# SOIC8-TSSOP8_v1_0.net
KiCad netlist of a schematic drawn in EAGLE
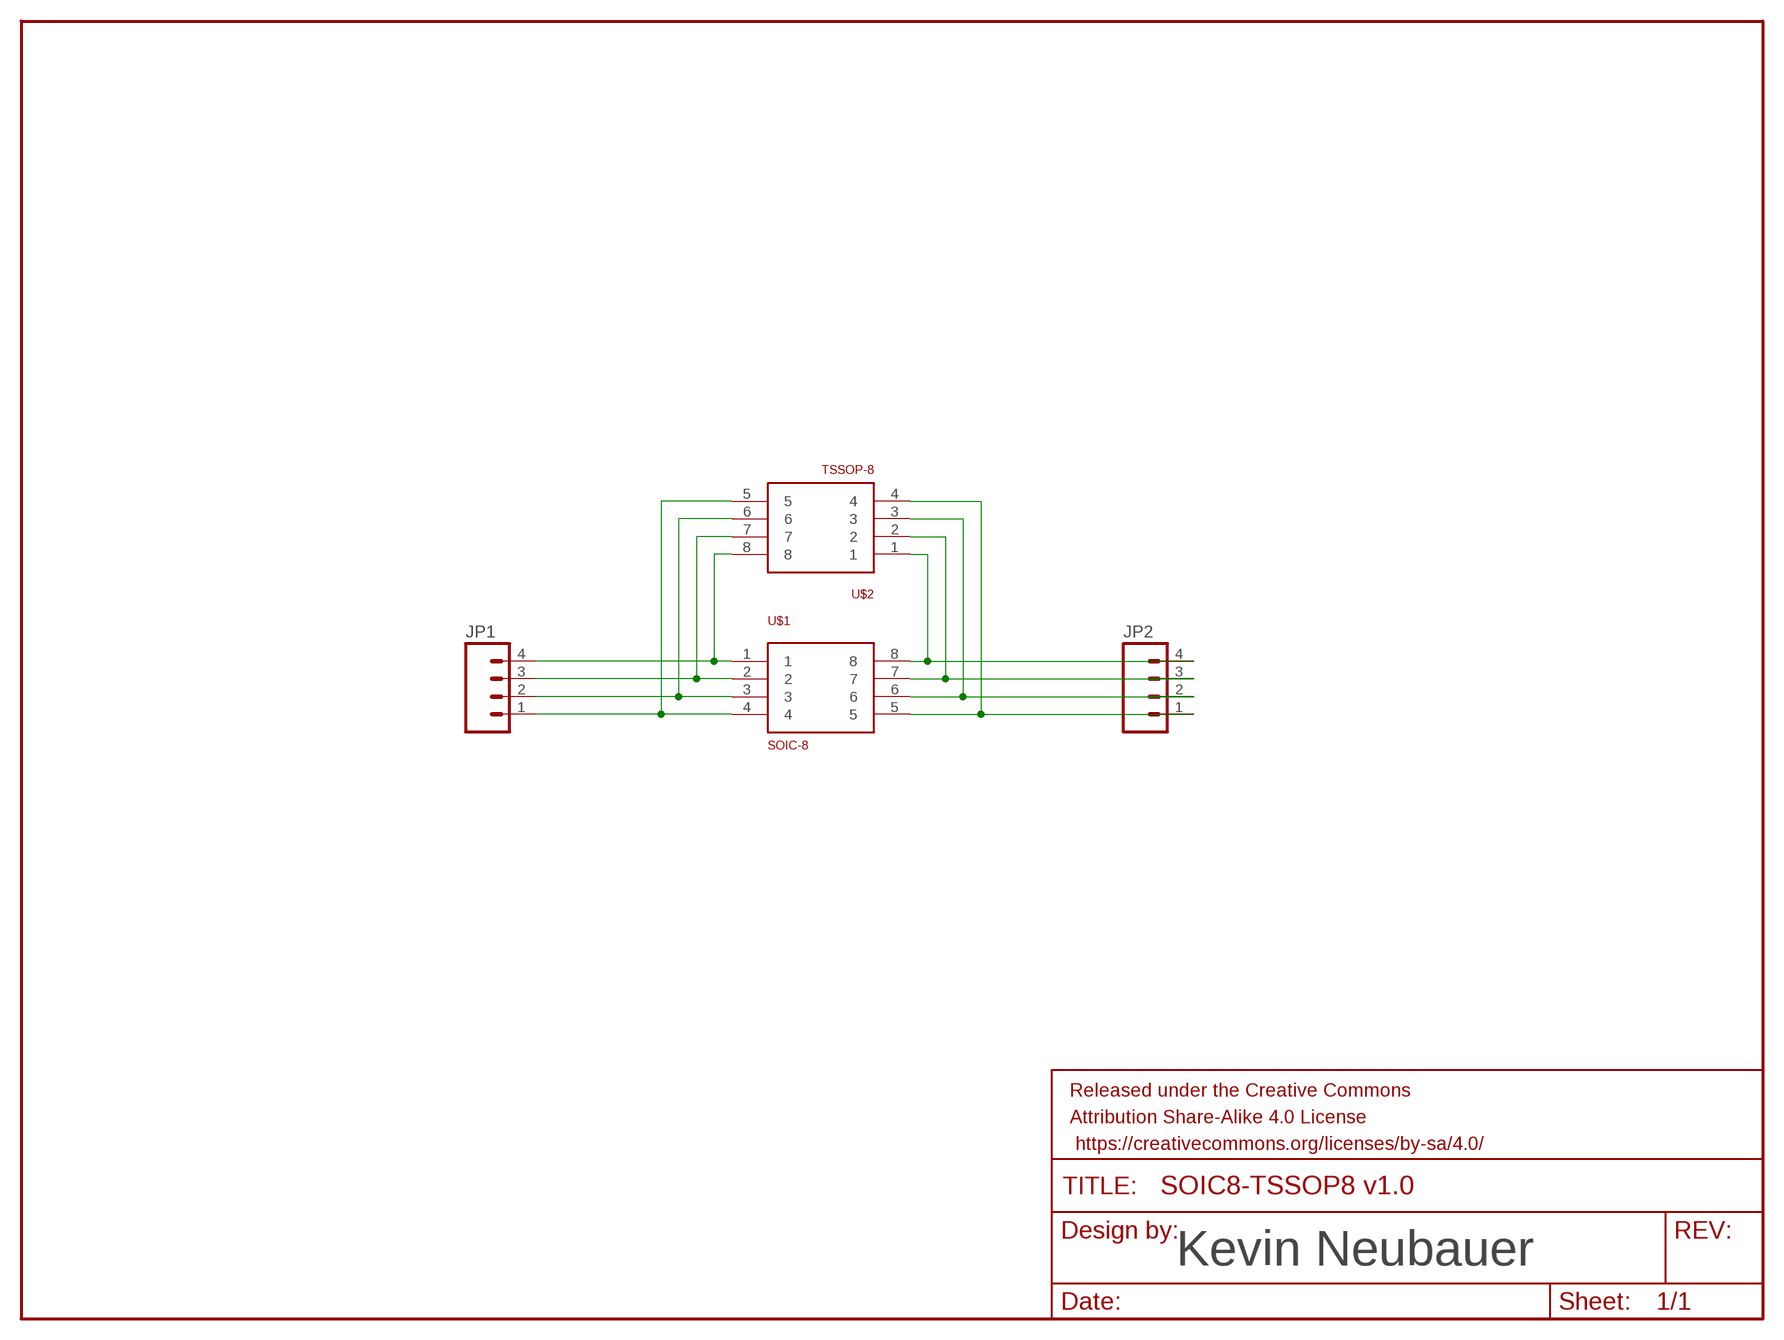
[diagram p0: schematic, sheet 1]

(export (version "E")
  (design (tool "Eeschema 10.0.6"))
  (components
    (comp (ref "FRAME1")
      (value "FRAME-LETTER")
      (footprint "eagle-import:CREATIVE_COMMONS")
      (libsource (lib "eagle-import") (part "FRAME-LETTER"))
    )
    (comp (ref "JP1")
      (value "M04PTH")
      (footprint "eagle-import:1X04")
      (libsource (lib "eagle-import") (part "M04PTH"))
    )
    (comp (ref "JP2")
      (value "M04PTH")
      (footprint "eagle-import:1X04")
      (libsource (lib "eagle-import") (part "M04PTH"))
    )
    (comp (ref "U$1")
      (value "SOIC-8")
      (footprint "eagle-import:SOIC-8")
      (libsource (lib "eagle-import") (part "SOIC-8"))
    )
    (comp (ref "U$2")
      (value "TSSOP-8")
      (footprint "eagle-import:TSSOP8")
      (libsource (lib "eagle-import") (part "TSSOP-8"))
    )
  )
  (nets
    (net (code "1") (name "Net-(JP1-Pad1)") (class "Default")
      (node (ref "JP1") (pin "1") (pinfunction "1_1") (pintype "passive"))
      (node (ref "U$1") (pin "4") (pinfunction "4_4") (pintype "bidirectional"))
      (node (ref "U$2") (pin "5") (pinfunction "5_5") (pintype "bidirectional"))
    )
    (net (code "2") (name "Net-(JP1-Pad2)") (class "Default")
      (node (ref "JP1") (pin "2") (pinfunction "2_2") (pintype "passive"))
      (node (ref "U$1") (pin "3") (pinfunction "3_3") (pintype "bidirectional"))
      (node (ref "U$2") (pin "6") (pinfunction "6_6") (pintype "bidirectional"))
    )
    (net (code "3") (name "Net-(JP1-Pad3)") (class "Default")
      (node (ref "JP1") (pin "3") (pinfunction "3_3") (pintype "passive"))
      (node (ref "U$1") (pin "2") (pinfunction "2_2") (pintype "bidirectional"))
      (node (ref "U$2") (pin "7") (pinfunction "7_7") (pintype "bidirectional"))
    )
    (net (code "4") (name "Net-(JP1-Pad4)") (class "Default")
      (node (ref "JP1") (pin "4") (pinfunction "4_4") (pintype "passive"))
      (node (ref "U$1") (pin "1") (pinfunction "1_1") (pintype "bidirectional"))
      (node (ref "U$2") (pin "8") (pinfunction "8_8") (pintype "bidirectional"))
    )
    (net (code "5") (name "Net-(JP2-Pad1)") (class "Default")
      (node (ref "JP2") (pin "1") (pinfunction "1_1") (pintype "passive"))
      (node (ref "U$1") (pin "5") (pinfunction "5_5") (pintype "bidirectional"))
      (node (ref "U$2") (pin "4") (pinfunction "4_4") (pintype "bidirectional"))
    )
    (net (code "6") (name "Net-(JP2-Pad2)") (class "Default")
      (node (ref "JP2") (pin "2") (pinfunction "2_2") (pintype "passive"))
      (node (ref "U$1") (pin "6") (pinfunction "6_6") (pintype "bidirectional"))
      (node (ref "U$2") (pin "3") (pinfunction "3_3") (pintype "bidirectional"))
    )
    (net (code "7") (name "Net-(JP2-Pad3)") (class "Default")
      (node (ref "JP2") (pin "3") (pinfunction "3_3") (pintype "passive"))
      (node (ref "U$1") (pin "7") (pinfunction "7_7") (pintype "bidirectional"))
      (node (ref "U$2") (pin "2") (pinfunction "2_2") (pintype "bidirectional"))
    )
    (net (code "8") (name "Net-(JP2-Pad4)") (class "Default")
      (node (ref "JP2") (pin "4") (pinfunction "4_4") (pintype "passive"))
      (node (ref "U$1") (pin "8") (pinfunction "8_8") (pintype "bidirectional"))
      (node (ref "U$2") (pin "1") (pinfunction "1_1") (pintype "bidirectional"))
    )
  )
)
